# Hammerhead_-_MAX11300_Breakout_Connector.net
KiCad netlist of a schematic drawn in Altium Designer
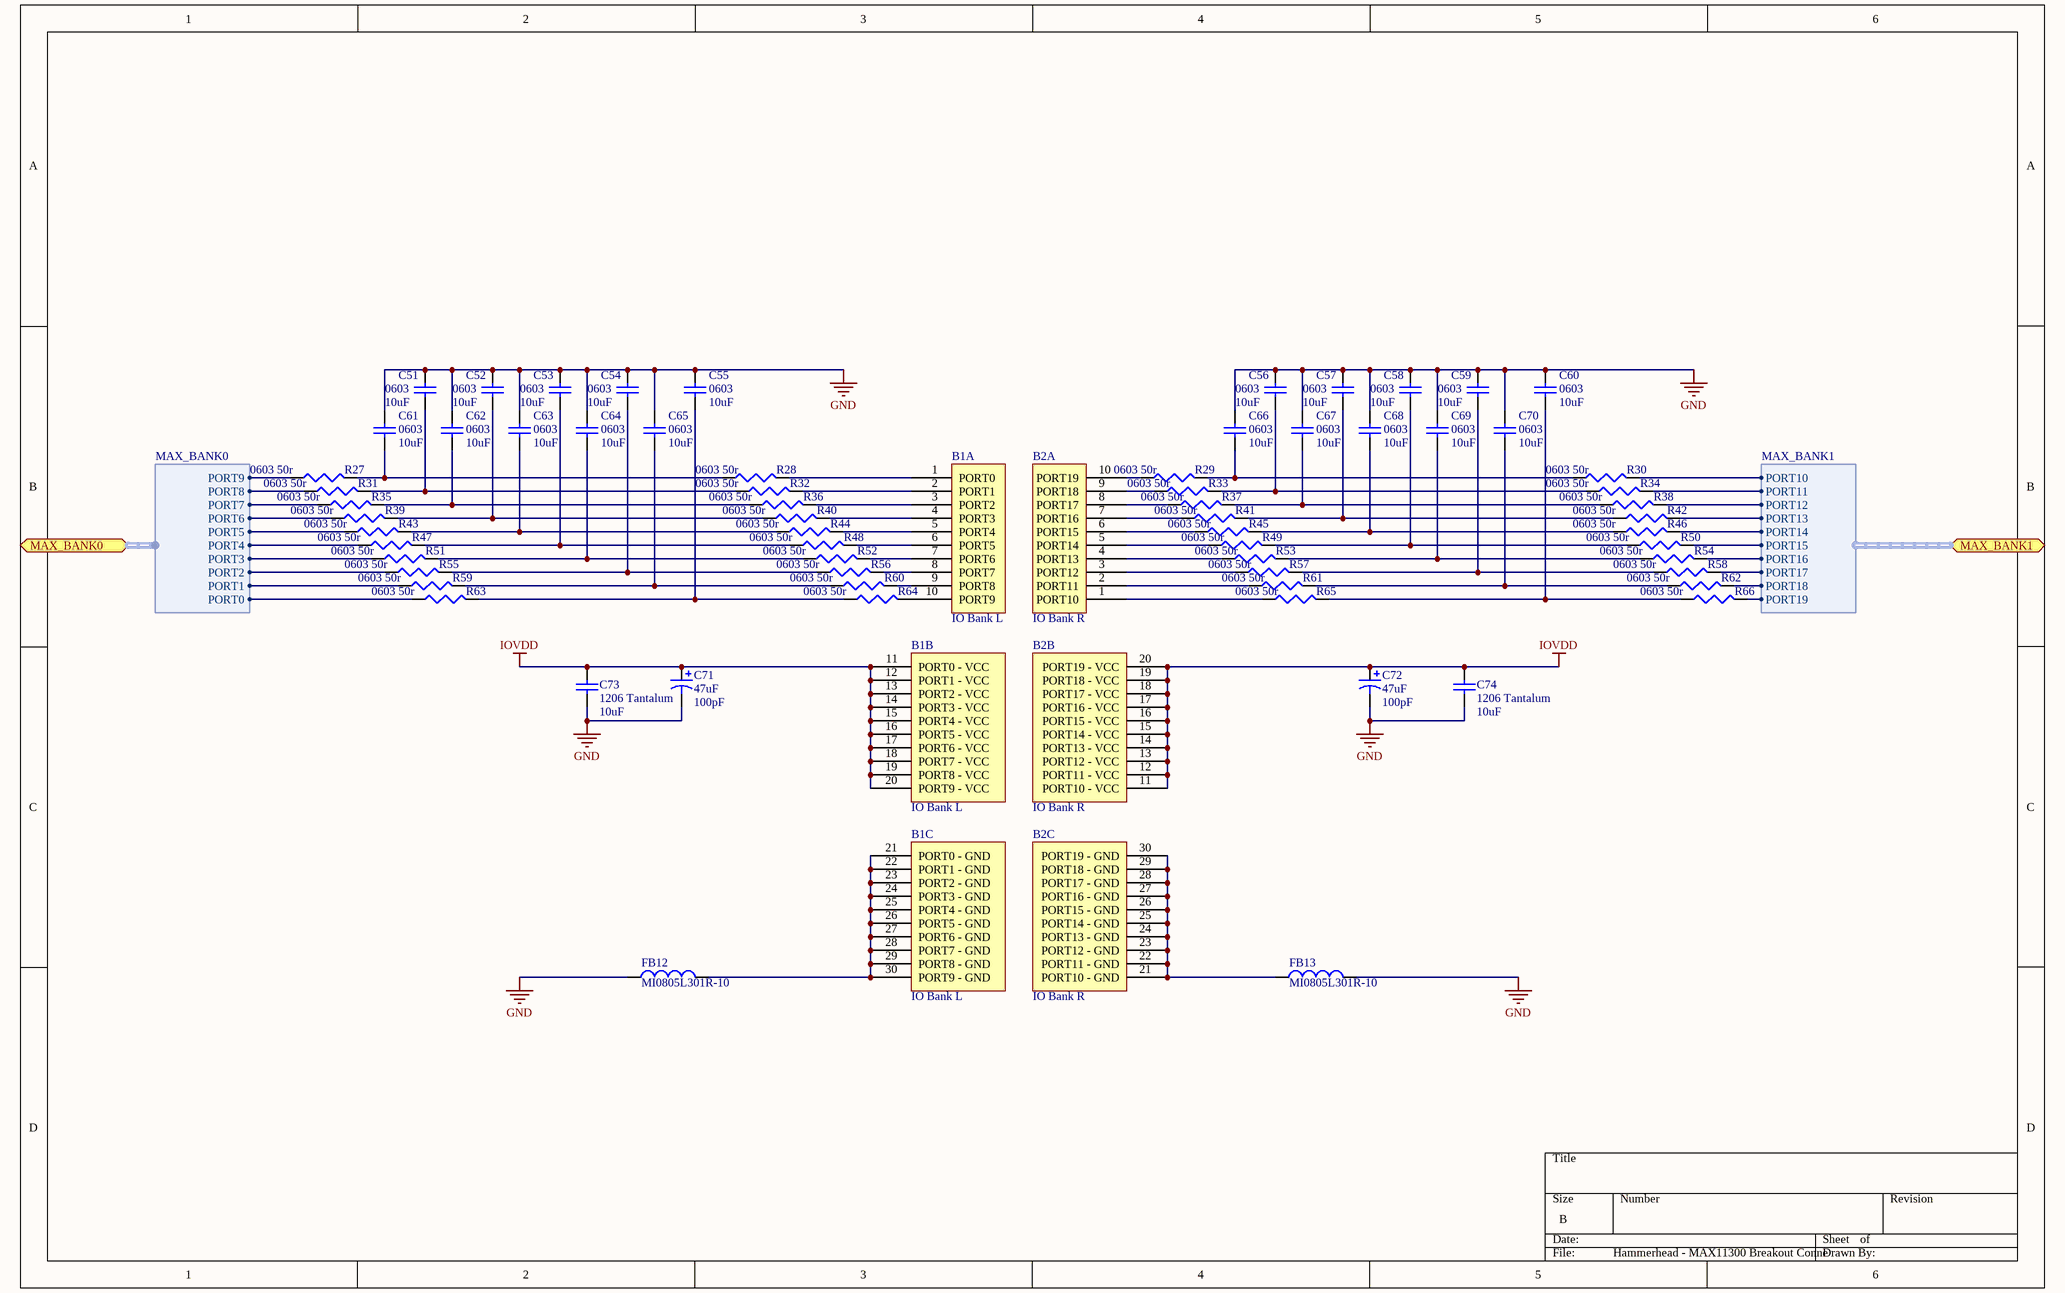
[diagram p0: Hammerhead - MAX11300 Breakout Connectors R1.1.SchDoc]

(export (version "E")
  (design (tool "Eeschema 10.0.6"))
  (components
    (comp (ref "B1")
      (value "IO Bank L")
      (footprint "2.54mm 10X3 Header")
      (libsource (lib "SunIO Schematic Symbol Lib") (part "IO Bank L"))
    )
    (comp (ref "B2")
      (value "IO Bank R")
      (footprint "2.54mm 10X3 Header")
      (libsource (lib "SunIO Schematic Symbol Lib") (part "IO Bank R"))
    )
    (comp (ref "C51")
      (value "0603")
      (footprint "1608[0603]")
      (description "Capacitor (Semiconductor SIM Model)")
      (fields (field (name "ALTIUM_VALUE") "10uF") (field (name "PUBLISHER") "Altium Limited"))
      (libsource (lib "Miscellaneous Devices") (part "Cap Semi"))
    )
    (comp (ref "C52")
      (value "0603")
      (footprint "1608[0603]")
      (description "Capacitor (Semiconductor SIM Model)")
      (fields (field (name "ALTIUM_VALUE") "10uF") (field (name "PUBLISHER") "Altium Limited"))
      (libsource (lib "Miscellaneous Devices") (part "Cap Semi"))
    )
    (comp (ref "C53")
      (value "0603")
      (footprint "1608[0603]")
      (description "Capacitor (Semiconductor SIM Model)")
      (fields (field (name "ALTIUM_VALUE") "10uF") (field (name "PUBLISHER") "Altium Limited"))
      (libsource (lib "Miscellaneous Devices") (part "Cap Semi"))
    )
    (comp (ref "C54")
      (value "0603")
      (footprint "1608[0603]")
      (description "Capacitor (Semiconductor SIM Model)")
      (fields (field (name "ALTIUM_VALUE") "10uF") (field (name "PUBLISHER") "Altium Limited"))
      (libsource (lib "Miscellaneous Devices") (part "Cap Semi"))
    )
    (comp (ref "C55")
      (value "0603")
      (footprint "1608[0603]")
      (description "Capacitor (Semiconductor SIM Model)")
      (fields (field (name "ALTIUM_VALUE") "10uF") (field (name "PUBLISHER") "Altium Limited"))
      (libsource (lib "Miscellaneous Devices") (part "Cap Semi"))
    )
    (comp (ref "C56")
      (value "0603")
      (footprint "1608[0603]")
      (description "Capacitor (Semiconductor SIM Model)")
      (fields (field (name "ALTIUM_VALUE") "10uF") (field (name "PUBLISHER") "Altium Limited"))
      (libsource (lib "Miscellaneous Devices") (part "Cap Semi"))
    )
    (comp (ref "C57")
      (value "0603")
      (footprint "1608[0603]")
      (description "Capacitor (Semiconductor SIM Model)")
      (fields (field (name "ALTIUM_VALUE") "10uF") (field (name "PUBLISHER") "Altium Limited"))
      (libsource (lib "Miscellaneous Devices") (part "Cap Semi"))
    )
    (comp (ref "C58")
      (value "0603")
      (footprint "1608[0603]")
      (description "Capacitor (Semiconductor SIM Model)")
      (fields (field (name "ALTIUM_VALUE") "10uF") (field (name "PUBLISHER") "Altium Limited"))
      (libsource (lib "Miscellaneous Devices") (part "Cap Semi"))
    )
    (comp (ref "C59")
      (value "0603")
      (footprint "1608[0603]")
      (description "Capacitor (Semiconductor SIM Model)")
      (fields (field (name "ALTIUM_VALUE") "10uF") (field (name "PUBLISHER") "Altium Limited"))
      (libsource (lib "Miscellaneous Devices") (part "Cap Semi"))
    )
    (comp (ref "C60")
      (value "0603")
      (footprint "1608[0603]")
      (description "Capacitor (Semiconductor SIM Model)")
      (fields (field (name "ALTIUM_VALUE") "10uF") (field (name "PUBLISHER") "Altium Limited"))
      (libsource (lib "Miscellaneous Devices") (part "Cap Semi"))
    )
    (comp (ref "C61")
      (value "0603")
      (footprint "1608[0603]")
      (description "Capacitor (Semiconductor SIM Model)")
      (fields (field (name "ALTIUM_VALUE") "10uF") (field (name "PUBLISHER") "Altium Limited"))
      (libsource (lib "Miscellaneous Devices") (part "Cap Semi"))
    )
    (comp (ref "C62")
      (value "0603")
      (footprint "1608[0603]")
      (description "Capacitor (Semiconductor SIM Model)")
      (fields (field (name "ALTIUM_VALUE") "10uF") (field (name "PUBLISHER") "Altium Limited"))
      (libsource (lib "Miscellaneous Devices") (part "Cap Semi"))
    )
    (comp (ref "C63")
      (value "0603")
      (footprint "1608[0603]")
      (description "Capacitor (Semiconductor SIM Model)")
      (fields (field (name "ALTIUM_VALUE") "10uF") (field (name "PUBLISHER") "Altium Limited"))
      (libsource (lib "Miscellaneous Devices") (part "Cap Semi"))
    )
    (comp (ref "C64")
      (value "0603")
      (footprint "1608[0603]")
      (description "Capacitor (Semiconductor SIM Model)")
      (fields (field (name "ALTIUM_VALUE") "10uF") (field (name "PUBLISHER") "Altium Limited"))
      (libsource (lib "Miscellaneous Devices") (part "Cap Semi"))
    )
    (comp (ref "C65")
      (value "0603")
      (footprint "1608[0603]")
      (description "Capacitor (Semiconductor SIM Model)")
      (fields (field (name "ALTIUM_VALUE") "10uF") (field (name "PUBLISHER") "Altium Limited"))
      (libsource (lib "Miscellaneous Devices") (part "Cap Semi"))
    )
    (comp (ref "C66")
      (value "0603")
      (footprint "1608[0603]")
      (description "Capacitor (Semiconductor SIM Model)")
      (fields (field (name "ALTIUM_VALUE") "10uF") (field (name "PUBLISHER") "Altium Limited"))
      (libsource (lib "Miscellaneous Devices") (part "Cap Semi"))
    )
    (comp (ref "C67")
      (value "0603")
      (footprint "1608[0603]")
      (description "Capacitor (Semiconductor SIM Model)")
      (fields (field (name "ALTIUM_VALUE") "10uF") (field (name "PUBLISHER") "Altium Limited"))
      (libsource (lib "Miscellaneous Devices") (part "Cap Semi"))
    )
    (comp (ref "C68")
      (value "0603")
      (footprint "1608[0603]")
      (description "Capacitor (Semiconductor SIM Model)")
      (fields (field (name "ALTIUM_VALUE") "10uF") (field (name "PUBLISHER") "Altium Limited"))
      (libsource (lib "Miscellaneous Devices") (part "Cap Semi"))
    )
    (comp (ref "C69")
      (value "0603")
      (footprint "1608[0603]")
      (description "Capacitor (Semiconductor SIM Model)")
      (fields (field (name "ALTIUM_VALUE") "10uF") (field (name "PUBLISHER") "Altium Limited"))
      (libsource (lib "Miscellaneous Devices") (part "Cap Semi"))
    )
    (comp (ref "C70")
      (value "0603")
      (footprint "1608[0603]")
      (description "Capacitor (Semiconductor SIM Model)")
      (fields (field (name "ALTIUM_VALUE") "10uF") (field (name "PUBLISHER") "Altium Limited"))
      (libsource (lib "Miscellaneous Devices") (part "Cap Semi"))
    )
    (comp (ref "C71")
      (value "47uF")
      (footprint "Panasonic VS C")
      (description "Polarized Capacitor (Radial)")
      (fields (field (name "ALTIUM_VALUE") "100pF") (field (name "PUBLISHER") "Altium Limited"))
      (libsource (lib "Miscellaneous Devices") (part "Cap Pol1"))
    )
    (comp (ref "C72")
      (value "47uF")
      (footprint "Panasonic VS C")
      (description "Polarized Capacitor (Radial)")
      (fields (field (name "ALTIUM_VALUE") "100pF") (field (name "PUBLISHER") "Altium Limited"))
      (libsource (lib "Miscellaneous Devices") (part "Cap Pol1"))
    )
    (comp (ref "C73")
      (value "1206 Tantalum")
      (footprint "C1206")
      (description "Capacitor (Semiconductor SIM Model)")
      (fields (field (name "ALTIUM_VALUE") "10uF") (field (name "PUBLISHER") "Altium Limited"))
      (libsource (lib "Miscellaneous Devices") (part "Cap Semi"))
    )
    (comp (ref "C74")
      (value "1206 Tantalum")
      (footprint "C1206")
      (description "Capacitor (Semiconductor SIM Model)")
      (fields (field (name "ALTIUM_VALUE") "10uF") (field (name "PUBLISHER") "Altium Limited"))
      (libsource (lib "Miscellaneous Devices") (part "Cap Semi"))
    )
    (comp (ref "FB12")
      (value "MI0805L301R-10")
      (footprint "SM 0805 - gap trimmed")
      (description "Inductor")
      (fields (field (name "PUBLISHER") "Altium Limited"))
      (libsource (lib "Miscellaneous Devices") (part "Inductor"))
    )
    (comp (ref "FB13")
      (value "MI0805L301R-10")
      (footprint "SM 0805 - gap trimmed")
      (description "Inductor")
      (fields (field (name "PUBLISHER") "Altium Limited"))
      (libsource (lib "Miscellaneous Devices") (part "Inductor"))
    )
    (comp (ref "R27")
      (value "0603")
      (footprint "J1-0603")
      (description "Resistor")
      (fields (field (name "ALTIUM_VALUE") "50r") (field (name "PUBLISHER") "Altium Limited"))
      (libsource (lib "Miscellaneous Devices") (part "Res3"))
    )
    (comp (ref "R28")
      (value "0603")
      (footprint "J1-0603")
      (description "Resistor")
      (fields (field (name "ALTIUM_VALUE") "50r") (field (name "PUBLISHER") "Altium Limited"))
      (libsource (lib "Miscellaneous Devices") (part "Res3"))
    )
    (comp (ref "R29")
      (value "0603")
      (footprint "J1-0603")
      (description "Resistor")
      (fields (field (name "ALTIUM_VALUE") "50r") (field (name "PUBLISHER") "Altium Limited"))
      (libsource (lib "Miscellaneous Devices") (part "Res3"))
    )
    (comp (ref "R30")
      (value "0603")
      (footprint "J1-0603")
      (description "Resistor")
      (fields (field (name "ALTIUM_VALUE") "50r") (field (name "PUBLISHER") "Altium Limited"))
      (libsource (lib "Miscellaneous Devices") (part "Res3"))
    )
    (comp (ref "R31")
      (value "0603")
      (footprint "J1-0603")
      (description "Resistor")
      (fields (field (name "ALTIUM_VALUE") "50r") (field (name "PUBLISHER") "Altium Limited"))
      (libsource (lib "Miscellaneous Devices") (part "Res3"))
    )
    (comp (ref "R32")
      (value "0603")
      (footprint "J1-0603")
      (description "Resistor")
      (fields (field (name "ALTIUM_VALUE") "50r") (field (name "PUBLISHER") "Altium Limited"))
      (libsource (lib "Miscellaneous Devices") (part "Res3"))
    )
    (comp (ref "R33")
      (value "0603")
      (footprint "J1-0603")
      (description "Resistor")
      (fields (field (name "ALTIUM_VALUE") "50r") (field (name "PUBLISHER") "Altium Limited"))
      (libsource (lib "Miscellaneous Devices") (part "Res3"))
    )
    (comp (ref "R34")
      (value "0603")
      (footprint "J1-0603")
      (description "Resistor")
      (fields (field (name "ALTIUM_VALUE") "50r") (field (name "PUBLISHER") "Altium Limited"))
      (libsource (lib "Miscellaneous Devices") (part "Res3"))
    )
    (comp (ref "R35")
      (value "0603")
      (footprint "J1-0603")
      (description "Resistor")
      (fields (field (name "ALTIUM_VALUE") "50r") (field (name "PUBLISHER") "Altium Limited"))
      (libsource (lib "Miscellaneous Devices") (part "Res3"))
    )
    (comp (ref "R36")
      (value "0603")
      (footprint "J1-0603")
      (description "Resistor")
      (fields (field (name "ALTIUM_VALUE") "50r") (field (name "PUBLISHER") "Altium Limited"))
      (libsource (lib "Miscellaneous Devices") (part "Res3"))
    )
    (comp (ref "R37")
      (value "0603")
      (footprint "J1-0603")
      (description "Resistor")
      (fields (field (name "ALTIUM_VALUE") "50r") (field (name "PUBLISHER") "Altium Limited"))
      (libsource (lib "Miscellaneous Devices") (part "Res3"))
    )
    (comp (ref "R38")
      (value "0603")
      (footprint "J1-0603")
      (description "Resistor")
      (fields (field (name "ALTIUM_VALUE") "50r") (field (name "PUBLISHER") "Altium Limited"))
      (libsource (lib "Miscellaneous Devices") (part "Res3"))
    )
    (comp (ref "R39")
      (value "0603")
      (footprint "J1-0603")
      (description "Resistor")
      (fields (field (name "ALTIUM_VALUE") "50r") (field (name "PUBLISHER") "Altium Limited"))
      (libsource (lib "Miscellaneous Devices") (part "Res3"))
    )
    (comp (ref "R40")
      (value "0603")
      (footprint "J1-0603")
      (description "Resistor")
      (fields (field (name "ALTIUM_VALUE") "50r") (field (name "PUBLISHER") "Altium Limited"))
      (libsource (lib "Miscellaneous Devices") (part "Res3"))
    )
    (comp (ref "R41")
      (value "0603")
      (footprint "J1-0603")
      (description "Resistor")
      (fields (field (name "ALTIUM_VALUE") "50r") (field (name "PUBLISHER") "Altium Limited"))
      (libsource (lib "Miscellaneous Devices") (part "Res3"))
    )
    (comp (ref "R42")
      (value "0603")
      (footprint "J1-0603")
      (description "Resistor")
      (fields (field (name "ALTIUM_VALUE") "50r") (field (name "PUBLISHER") "Altium Limited"))
      (libsource (lib "Miscellaneous Devices") (part "Res3"))
    )
    (comp (ref "R43")
      (value "0603")
      (footprint "J1-0603")
      (description "Resistor")
      (fields (field (name "ALTIUM_VALUE") "50r") (field (name "PUBLISHER") "Altium Limited"))
      (libsource (lib "Miscellaneous Devices") (part "Res3"))
    )
    (comp (ref "R44")
      (value "0603")
      (footprint "J1-0603")
      (description "Resistor")
      (fields (field (name "ALTIUM_VALUE") "50r") (field (name "PUBLISHER") "Altium Limited"))
      (libsource (lib "Miscellaneous Devices") (part "Res3"))
    )
    (comp (ref "R45")
      (value "0603")
      (footprint "J1-0603")
      (description "Resistor")
      (fields (field (name "ALTIUM_VALUE") "50r") (field (name "PUBLISHER") "Altium Limited"))
      (libsource (lib "Miscellaneous Devices") (part "Res3"))
    )
    (comp (ref "R46")
      (value "0603")
      (footprint "J1-0603")
      (description "Resistor")
      (fields (field (name "ALTIUM_VALUE") "50r") (field (name "PUBLISHER") "Altium Limited"))
      (libsource (lib "Miscellaneous Devices") (part "Res3"))
    )
    (comp (ref "R47")
      (value "0603")
      (footprint "J1-0603")
      (description "Resistor")
      (fields (field (name "ALTIUM_VALUE") "50r") (field (name "PUBLISHER") "Altium Limited"))
      (libsource (lib "Miscellaneous Devices") (part "Res3"))
    )
    (comp (ref "R48")
      (value "0603")
      (footprint "J1-0603")
      (description "Resistor")
      (fields (field (name "ALTIUM_VALUE") "50r") (field (name "PUBLISHER") "Altium Limited"))
      (libsource (lib "Miscellaneous Devices") (part "Res3"))
    )
    (comp (ref "R49")
      (value "0603")
      (footprint "J1-0603")
      (description "Resistor")
      (fields (field (name "ALTIUM_VALUE") "50r") (field (name "PUBLISHER") "Altium Limited"))
      (libsource (lib "Miscellaneous Devices") (part "Res3"))
    )
    (comp (ref "R50")
      (value "0603")
      (footprint "J1-0603")
      (description "Resistor")
      (fields (field (name "ALTIUM_VALUE") "50r") (field (name "PUBLISHER") "Altium Limited"))
      (libsource (lib "Miscellaneous Devices") (part "Res3"))
    )
    (comp (ref "R51")
      (value "0603")
      (footprint "J1-0603")
      (description "Resistor")
      (fields (field (name "ALTIUM_VALUE") "50r") (field (name "PUBLISHER") "Altium Limited"))
      (libsource (lib "Miscellaneous Devices") (part "Res3"))
    )
    (comp (ref "R52")
      (value "0603")
      (footprint "J1-0603")
      (description "Resistor")
      (fields (field (name "ALTIUM_VALUE") "50r") (field (name "PUBLISHER") "Altium Limited"))
      (libsource (lib "Miscellaneous Devices") (part "Res3"))
    )
    (comp (ref "R53")
      (value "0603")
      (footprint "J1-0603")
      (description "Resistor")
      (fields (field (name "ALTIUM_VALUE") "50r") (field (name "PUBLISHER") "Altium Limited"))
      (libsource (lib "Miscellaneous Devices") (part "Res3"))
    )
    (comp (ref "R54")
      (value "0603")
      (footprint "J1-0603")
      (description "Resistor")
      (fields (field (name "ALTIUM_VALUE") "50r") (field (name "PUBLISHER") "Altium Limited"))
      (libsource (lib "Miscellaneous Devices") (part "Res3"))
    )
    (comp (ref "R55")
      (value "0603")
      (footprint "J1-0603")
      (description "Resistor")
      (fields (field (name "ALTIUM_VALUE") "50r") (field (name "PUBLISHER") "Altium Limited"))
      (libsource (lib "Miscellaneous Devices") (part "Res3"))
    )
    (comp (ref "R56")
      (value "0603")
      (footprint "J1-0603")
      (description "Resistor")
      (fields (field (name "ALTIUM_VALUE") "50r") (field (name "PUBLISHER") "Altium Limited"))
      (libsource (lib "Miscellaneous Devices") (part "Res3"))
    )
    (comp (ref "R57")
      (value "0603")
      (footprint "J1-0603")
      (description "Resistor")
      (fields (field (name "ALTIUM_VALUE") "50r") (field (name "PUBLISHER") "Altium Limited"))
      (libsource (lib "Miscellaneous Devices") (part "Res3"))
    )
    (comp (ref "R58")
      (value "0603")
      (footprint "J1-0603")
      (description "Resistor")
      (fields (field (name "ALTIUM_VALUE") "50r") (field (name "PUBLISHER") "Altium Limited"))
      (libsource (lib "Miscellaneous Devices") (part "Res3"))
    )
    (comp (ref "R59")
      (value "0603")
      (footprint "J1-0603")
      (description "Resistor")
      (fields (field (name "ALTIUM_VALUE") "50r") (field (name "PUBLISHER") "Altium Limited"))
      (libsource (lib "Miscellaneous Devices") (part "Res3"))
    )
    (comp (ref "R60")
      (value "0603")
      (footprint "J1-0603")
      (description "Resistor")
      (fields (field (name "ALTIUM_VALUE") "50r") (field (name "PUBLISHER") "Altium Limited"))
      (libsource (lib "Miscellaneous Devices") (part "Res3"))
    )
    (comp (ref "R61")
      (value "0603")
      (footprint "J1-0603")
      (description "Resistor")
      (fields (field (name "ALTIUM_VALUE") "50r") (field (name "PUBLISHER") "Altium Limited"))
      (libsource (lib "Miscellaneous Devices") (part "Res3"))
    )
    (comp (ref "R62")
      (value "0603")
      (footprint "J1-0603")
      (description "Resistor")
      (fields (field (name "ALTIUM_VALUE") "50r") (field (name "PUBLISHER") "Altium Limited"))
      (libsource (lib "Miscellaneous Devices") (part "Res3"))
    )
    (comp (ref "R63")
      (value "0603")
      (footprint "J1-0603")
      (description "Resistor")
      (fields (field (name "ALTIUM_VALUE") "50r") (field (name "PUBLISHER") "Altium Limited"))
      (libsource (lib "Miscellaneous Devices") (part "Res3"))
    )
    (comp (ref "R64")
      (value "0603")
      (footprint "J1-0603")
      (description "Resistor")
      (fields (field (name "ALTIUM_VALUE") "50r") (field (name "PUBLISHER") "Altium Limited"))
      (libsource (lib "Miscellaneous Devices") (part "Res3"))
    )
    (comp (ref "R65")
      (value "0603")
      (footprint "J1-0603")
      (description "Resistor")
      (fields (field (name "ALTIUM_VALUE") "50r") (field (name "PUBLISHER") "Altium Limited"))
      (libsource (lib "Miscellaneous Devices") (part "Res3"))
    )
    (comp (ref "R66")
      (value "0603")
      (footprint "J1-0603")
      (description "Resistor")
      (fields (field (name "ALTIUM_VALUE") "50r") (field (name "PUBLISHER") "Altium Limited"))
      (libsource (lib "Miscellaneous Devices") (part "Res3"))
    )
  )
  (nets
    (net (code "3") (name "/PORT0") (class "Default")
      (node (ref "R63") (pin "1") (pinfunction "1_1") (pintype "passive"))
    )
    (net (code "4") (name "/PORT1") (class "Default")
      (node (ref "R59") (pin "1") (pinfunction "1_1") (pintype "passive"))
    )
    (net (code "5") (name "/PORT2") (class "Default")
      (node (ref "R55") (pin "1") (pinfunction "1_1") (pintype "passive"))
    )
    (net (code "6") (name "/PORT3") (class "Default")
      (node (ref "R51") (pin "1") (pinfunction "1_1") (pintype "passive"))
    )
    (net (code "7") (name "/PORT4") (class "Default")
      (node (ref "R47") (pin "1") (pinfunction "1_1") (pintype "passive"))
    )
    (net (code "8") (name "/PORT5") (class "Default")
      (node (ref "R43") (pin "1") (pinfunction "1_1") (pintype "passive"))
    )
    (net (code "9") (name "/PORT6") (class "Default")
      (node (ref "R39") (pin "1") (pinfunction "1_1") (pintype "passive"))
    )
    (net (code "10") (name "/PORT7") (class "Default")
      (node (ref "R35") (pin "1") (pinfunction "1_1") (pintype "passive"))
    )
    (net (code "11") (name "/PORT8") (class "Default")
      (node (ref "R31") (pin "1") (pinfunction "1_1") (pintype "passive"))
    )
    (net (code "12") (name "/PORT9") (class "Default")
      (node (ref "R27") (pin "1") (pinfunction "1_1") (pintype "passive"))
    )
    (net (code "13") (name "/PORT10") (class "Default")
      (node (ref "R30") (pin "2") (pinfunction "2_2") (pintype "passive"))
    )
    (net (code "14") (name "/PORT11") (class "Default")
      (node (ref "R34") (pin "2") (pinfunction "2_2") (pintype "passive"))
    )
    (net (code "15") (name "/PORT12") (class "Default")
      (node (ref "R38") (pin "2") (pinfunction "2_2") (pintype "passive"))
    )
    (net (code "16") (name "/PORT13") (class "Default")
      (node (ref "R42") (pin "2") (pinfunction "2_2") (pintype "passive"))
    )
    (net (code "17") (name "/PORT14") (class "Default")
      (node (ref "R46") (pin "2") (pinfunction "2_2") (pintype "passive"))
    )
    (net (code "18") (name "/PORT15") (class "Default")
      (node (ref "R50") (pin "2") (pinfunction "2_2") (pintype "passive"))
    )
    (net (code "19") (name "/PORT16") (class "Default")
      (node (ref "R54") (pin "2") (pinfunction "2_2") (pintype "passive"))
    )
    (net (code "20") (name "/PORT17") (class "Default")
      (node (ref "R58") (pin "2") (pinfunction "2_2") (pintype "passive"))
    )
    (net (code "21") (name "/PORT18") (class "Default")
      (node (ref "R62") (pin "2") (pinfunction "2_2") (pintype "passive"))
    )
    (net (code "22") (name "/PORT19") (class "Default")
      (node (ref "R66") (pin "2") (pinfunction "2_2") (pintype "passive"))
    )
    (net (code "25") (name "GND") (class "Default")
      (node (ref "C51") (pin "2") (pinfunction "2_2") (pintype "passive"))
      (node (ref "C52") (pin "2") (pinfunction "2_2") (pintype "passive"))
      (node (ref "C53") (pin "2") (pinfunction "2_2") (pintype "passive"))
      (node (ref "C54") (pin "2") (pinfunction "2_2") (pintype "passive"))
      (node (ref "C55") (pin "2") (pinfunction "2_2") (pintype "passive"))
      (node (ref "C56") (pin "2") (pinfunction "2_2") (pintype "passive"))
      (node (ref "C57") (pin "2") (pinfunction "2_2") (pintype "passive"))
      (node (ref "C58") (pin "2") (pinfunction "2_2") (pintype "passive"))
      (node (ref "C59") (pin "2") (pinfunction "2_2") (pintype "passive"))
      (node (ref "C60") (pin "2") (pinfunction "2_2") (pintype "passive"))
      (node (ref "C61") (pin "2") (pinfunction "2_2") (pintype "passive"))
      (node (ref "C62") (pin "2") (pinfunction "2_2") (pintype "passive"))
      (node (ref "C63") (pin "2") (pinfunction "2_2") (pintype "passive"))
      (node (ref "C64") (pin "2") (pinfunction "2_2") (pintype "passive"))
      (node (ref "C65") (pin "2") (pinfunction "2_2") (pintype "passive"))
      (node (ref "C66") (pin "2") (pinfunction "2_2") (pintype "passive"))
      (node (ref "C67") (pin "2") (pinfunction "2_2") (pintype "passive"))
      (node (ref "C68") (pin "2") (pinfunction "2_2") (pintype "passive"))
      (node (ref "C69") (pin "2") (pinfunction "2_2") (pintype "passive"))
      (node (ref "C70") (pin "2") (pinfunction "2_2") (pintype "passive"))
      (node (ref "C71") (pin "2") (pinfunction "2_2") (pintype "passive"))
      (node (ref "C72") (pin "2") (pinfunction "2_2") (pintype "passive"))
      (node (ref "C73") (pin "1") (pinfunction "1_1") (pintype "passive"))
      (node (ref "C74") (pin "1") (pinfunction "1_1") (pintype "passive"))
      (node (ref "FB12") (pin "1") (pinfunction "1_1") (pintype "passive"))
      (node (ref "FB13") (pin "2") (pinfunction "2_2") (pintype "passive"))
    )
    (net (code "26") (name "IOVDD") (class "Default")
      (node (ref "B1") (pin "11") (pinfunction "PORT0_-_VCC_11") (pintype "passive"))
      (node (ref "B1") (pin "12") (pinfunction "PORT1_-_VCC_12") (pintype "passive"))
      (node (ref "B1") (pin "13") (pinfunction "PORT2_-_VCC_13") (pintype "passive"))
      (node (ref "B1") (pin "14") (pinfunction "PORT3_-_VCC_14") (pintype "passive"))
      (node (ref "B1") (pin "15") (pinfunction "PORT4_-_VCC_15") (pintype "passive"))
      (node (ref "B1") (pin "16") (pinfunction "PORT5_-_VCC_16") (pintype "passive"))
      (node (ref "B1") (pin "17") (pinfunction "PORT6_-_VCC_17") (pintype "passive"))
      (node (ref "B1") (pin "18") (pinfunction "PORT7_-_VCC_18") (pintype "passive"))
      (node (ref "B1") (pin "19") (pinfunction "PORT8_-_VCC_19") (pintype "passive"))
      (node (ref "B1") (pin "20") (pinfunction "PORT9_-_VCC_20") (pintype "passive"))
      (node (ref "B2") (pin "11") (pinfunction "PORT10_-_VCC_11") (pintype "passive"))
      (node (ref "B2") (pin "12") (pinfunction "PORT11_-_VCC_12") (pintype "passive"))
      (node (ref "B2") (pin "13") (pinfunction "PORT12_-_VCC_13") (pintype "passive"))
      (node (ref "B2") (pin "14") (pinfunction "PORT13_-_VCC_14") (pintype "passive"))
      (node (ref "B2") (pin "15") (pinfunction "PORT14_-_VCC_15") (pintype "passive"))
      (node (ref "B2") (pin "16") (pinfunction "PORT15_-_VCC_16") (pintype "passive"))
      (node (ref "B2") (pin "17") (pinfunction "PORT16_-_VCC_17") (pintype "passive"))
      (node (ref "B2") (pin "18") (pinfunction "PORT17_-_VCC_18") (pintype "passive"))
      (node (ref "B2") (pin "19") (pinfunction "PORT18_-_VCC_19") (pintype "passive"))
      (node (ref "B2") (pin "20") (pinfunction "PORT19_-_VCC_20") (pintype "passive"))
      (node (ref "C71") (pin "1") (pinfunction "1_1") (pintype "passive"))
      (node (ref "C72") (pin "1") (pinfunction "1_1") (pintype "passive"))
      (node (ref "C73") (pin "2") (pinfunction "2_2") (pintype "passive"))
      (node (ref "C74") (pin "2") (pinfunction "2_2") (pintype "passive"))
    )
    (net (code "27") (name "Net-(B1A-PORT0)") (class "Default")
      (node (ref "B1") (pin "1") (pinfunction "PORT0_1") (pintype "passive"))
      (node (ref "R28") (pin "2") (pinfunction "2_2") (pintype "passive"))
    )
    (net (code "28") (name "Net-(B1A-PORT1)") (class "Default")
      (node (ref "B1") (pin "2") (pinfunction "PORT1_2") (pintype "passive"))
      (node (ref "R32") (pin "2") (pinfunction "2_2") (pintype "passive"))
    )
    (net (code "29") (name "Net-(B1A-PORT2)") (class "Default")
      (node (ref "B1") (pin "3") (pinfunction "PORT2_3") (pintype "passive"))
      (node (ref "R36") (pin "2") (pinfunction "2_2") (pintype "passive"))
    )
    (net (code "30") (name "Net-(B1A-PORT3)") (class "Default")
      (node (ref "B1") (pin "4") (pinfunction "PORT3_4") (pintype "passive"))
      (node (ref "R40") (pin "2") (pinfunction "2_2") (pintype "passive"))
    )
    (net (code "31") (name "Net-(B1A-PORT4)") (class "Default")
      (node (ref "B1") (pin "5") (pinfunction "PORT4_5") (pintype "passive"))
      (node (ref "R44") (pin "2") (pinfunction "2_2") (pintype "passive"))
    )
    (net (code "32") (name "Net-(B1A-PORT5)") (class "Default")
      (node (ref "B1") (pin "6") (pinfunction "PORT5_6") (pintype "passive"))
      (node (ref "R48") (pin "2") (pinfunction "2_2") (pintype "passive"))
    )
    (net (code "33") (name "Net-(B1A-PORT6)") (class "Default")
      (node (ref "B1") (pin "7") (pinfunction "PORT6_7") (pintype "passive"))
      (node (ref "R52") (pin "2") (pinfunction "2_2") (pintype "passive"))
    )
    (net (code "34") (name "Net-(B1A-PORT7)") (class "Default")
      (node (ref "B1") (pin "8") (pinfunction "PORT7_8") (pintype "passive"))
      (node (ref "R56") (pin "2") (pinfunction "2_2") (pintype "passive"))
    )
    (net (code "35") (name "Net-(B1A-PORT8)") (class "Default")
      (node (ref "B1") (pin "9") (pinfunction "PORT8_9") (pintype "passive"))
      (node (ref "R60") (pin "2") (pinfunction "2_2") (pintype "passive"))
    )
    (net (code "36") (name "Net-(B1A-PORT9)") (class "Default")
      (node (ref "B1") (pin "10") (pinfunction "PORT9_10") (pintype "passive"))
      (node (ref "R64") (pin "2") (pinfunction "2_2") (pintype "passive"))
    )
    (net (code "37") (name "Net-(B1C-PORT0_-_GND)") (class "Default")
      (node (ref "B1") (pin "21") (pinfunction "PORT0_-_GND_21") (pintype "passive"))
      (node (ref "B1") (pin "22") (pinfunction "PORT1_-_GND_22") (pintype "passive"))
      (node (ref "B1") (pin "23") (pinfunction "PORT2_-_GND_23") (pintype "passive"))
      (node (ref "B1") (pin "24") (pinfunction "PORT3_-_GND_24") (pintype "passive"))
      (node (ref "B1") (pin "25") (pinfunction "PORT4_-_GND_25") (pintype "passive"))
      (node (ref "B1") (pin "26") (pinfunction "PORT5_-_GND_26") (pintype "passive"))
      (node (ref "B1") (pin "27") (pinfunction "PORT6_-_GND_27") (pintype "passive"))
      (node (ref "B1") (pin "28") (pinfunction "PORT7_-_GND_28") (pintype "passive"))
      (node (ref "B1") (pin "29") (pinfunction "PORT8_-_GND_29") (pintype "passive"))
      (node (ref "B1") (pin "30") (pinfunction "PORT9_-_GND_30") (pintype "passive"))
      (node (ref "FB12") (pin "2") (pinfunction "2_2") (pintype "passive"))
    )
    (net (code "38") (name "Net-(B2A-PORT10)") (class "Default")
      (node (ref "B2") (pin "1") (pinfunction "PORT10_1") (pintype "passive"))
      (node (ref "R65") (pin "1") (pinfunction "1_1") (pintype "passive"))
    )
    (net (code "39") (name "Net-(B2A-PORT11)") (class "Default")
      (node (ref "B2") (pin "2") (pinfunction "PORT11_2") (pintype "passive"))
      (node (ref "R61") (pin "1") (pinfunction "1_1") (pintype "passive"))
    )
    (net (code "40") (name "Net-(B2A-PORT12)") (class "Default")
      (node (ref "B2") (pin "3") (pinfunction "PORT12_3") (pintype "passive"))
      (node (ref "R57") (pin "1") (pinfunction "1_1") (pintype "passive"))
    )
    (net (code "41") (name "Net-(B2A-PORT13)") (class "Default")
      (node (ref "B2") (pin "4") (pinfunction "PORT13_4") (pintype "passive"))
      (node (ref "R53") (pin "1") (pinfunction "1_1") (pintype "passive"))
    )
    (net (code "42") (name "Net-(B2A-PORT14)") (class "Default")
      (node (ref "B2") (pin "5") (pinfunction "PORT14_5") (pintype "passive"))
      (node (ref "R49") (pin "1") (pinfunction "1_1") (pintype "passive"))
    )
    (net (code "43") (name "Net-(B2A-PORT15)") (class "Default")
      (node (ref "B2") (pin "6") (pinfunction "PORT15_6") (pintype "passive"))
      (node (ref "R45") (pin "1") (pinfunction "1_1") (pintype "passive"))
    )
    (net (code "44") (name "Net-(B2A-PORT16)") (class "Default")
      (node (ref "B2") (pin "7") (pinfunction "PORT16_7") (pintype "passive"))
      (node (ref "R41") (pin "1") (pinfunction "1_1") (pintype "passive"))
    )
    (net (code "45") (name "Net-(B2A-PORT17)") (class "Default")
      (node (ref "B2") (pin "8") (pinfunction "PORT17_8") (pintype "passive"))
      (node (ref "R37") (pin "1") (pinfunction "1_1") (pintype "passive"))
    )
    (net (code "46") (name "Net-(B2A-PORT18)") (class "Default")
      (node (ref "B2") (pin "9") (pinfunction "PORT18_9") (pintype "passive"))
      (node (ref "R33") (pin "1") (pinfunction "1_1") (pintype "passive"))
    )
    (net (code "47") (name "Net-(B2A-PORT19)") (class "Default")
      (node (ref "B2") (pin "10") (pinfunction "PORT19_10") (pintype "passive"))
      (node (ref "R29") (pin "1") (pinfunction "1_1") (pintype "passive"))
    )
    (net (code "48") (name "Net-(B2C-PORT10_-_GND)") (class "Default")
      (node (ref "B2") (pin "21") (pinfunction "PORT10_-_GND_21") (pintype "passive"))
      (node (ref "B2") (pin "22") (pinfunction "PORT11_-_GND_22") (pintype "passive"))
      (node (ref "B2") (pin "23") (pinfunction "PORT12_-_GND_23") (pintype "passive"))
      (node (ref "B2") (pin "24") (pinfunction "PORT13_-_GND_24") (pintype "passive"))
      (node (ref "B2") (pin "25") (pinfunction "PORT14_-_GND_25") (pintype "passive"))
      (node (ref "B2") (pin "26") (pinfunction "PORT15_-_GND_26") (pintype "passive"))
      (node (ref "B2") (pin "27") (pinfunction "PORT16_-_GND_27") (pintype "passive"))
      (node (ref "B2") (pin "28") (pinfunction "PORT17_-_GND_28") (pintype "passive"))
      (node (ref "B2") (pin "29") (pinfunction "PORT18_-_GND_29") (pintype "passive"))
      (node (ref "B2") (pin "30") (pinfunction "PORT19_-_GND_30") (pintype "passive"))
      (node (ref "FB13") (pin "1") (pinfunction "1_1") (pintype "passive"))
    )
    (net (code "49") (name "Net-(C51-Pad1)") (class "Default")
      (node (ref "C51") (pin "1") (pinfunction "1_1") (pintype "passive"))
      (node (ref "R31") (pin "2") (pinfunction "2_2") (pintype "passive"))
      (node (ref "R32") (pin "1") (pinfunction "1_1") (pintype "passive"))
    )
    (net (code "50") (name "Net-(C52-Pad1)") (class "Default")
      (node (ref "C52") (pin "1") (pinfunction "1_1") (pintype "passive"))
      (node (ref "R39") (pin "2") (pinfunction "2_2") (pintype "passive"))
      (node (ref "R40") (pin "1") (pinfunction "1_1") (pintype "passive"))
    )
    (net (code "51") (name "Net-(C53-Pad1)") (class "Default")
      (node (ref "C53") (pin "1") (pinfunction "1_1") (pintype "passive"))
      (node (ref "R47") (pin "2") (pinfunction "2_2") (pintype "passive"))
      (node (ref "R48") (pin "1") (pinfunction "1_1") (pintype "passive"))
    )
    (net (code "52") (name "Net-(C54-Pad1)") (class "Default")
      (node (ref "C54") (pin "1") (pinfunction "1_1") (pintype "passive"))
      (node (ref "R55") (pin "2") (pinfunction "2_2") (pintype "passive"))
      (node (ref "R56") (pin "1") (pinfunction "1_1") (pintype "passive"))
    )
    (net (code "53") (name "Net-(C55-Pad1)") (class "Default")
      (node (ref "C55") (pin "1") (pinfunction "1_1") (pintype "passive"))
      (node (ref "R63") (pin "2") (pinfunction "2_2") (pintype "passive"))
      (node (ref "R64") (pin "1") (pinfunction "1_1") (pintype "passive"))
    )
    (net (code "54") (name "Net-(C56-Pad1)") (class "Default")
      (node (ref "C56") (pin "1") (pinfunction "1_1") (pintype "passive"))
      (node (ref "R33") (pin "2") (pinfunction "2_2") (pintype "passive"))
      (node (ref "R34") (pin "1") (pinfunction "1_1") (pintype "passive"))
    )
    (net (code "55") (name "Net-(C57-Pad1)") (class "Default")
      (node (ref "C57") (pin "1") (pinfunction "1_1") (pintype "passive"))
      (node (ref "R41") (pin "2") (pinfunction "2_2") (pintype "passive"))
      (node (ref "R42") (pin "1") (pinfunction "1_1") (pintype "passive"))
    )
    (net (code "56") (name "Net-(C58-Pad1)") (class "Default")
      (node (ref "C58") (pin "1") (pinfunction "1_1") (pintype "passive"))
      (node (ref "R49") (pin "2") (pinfunction "2_2") (pintype "passive"))
      (node (ref "R50") (pin "1") (pinfunction "1_1") (pintype "passive"))
    )
    (net (code "57") (name "Net-(C59-Pad1)") (class "Default")
      (node (ref "C59") (pin "1") (pinfunction "1_1") (pintype "passive"))
      (node (ref "R57") (pin "2") (pinfunction "2_2") (pintype "passive"))
      (node (ref "R58") (pin "1") (pinfunction "1_1") (pintype "passive"))
    )
    (net (code "58") (name "Net-(C60-Pad1)") (class "Default")
      (node (ref "C60") (pin "1") (pinfunction "1_1") (pintype "passive"))
      (node (ref "R65") (pin "2") (pinfunction "2_2") (pintype "passive"))
      (node (ref "R66") (pin "1") (pinfunction "1_1") (pintype "passive"))
    )
    (net (code "59") (name "Net-(C61-Pad1)") (class "Default")
      (node (ref "C61") (pin "1") (pinfunction "1_1") (pintype "passive"))
      (node (ref "R27") (pin "2") (pinfunction "2_2") (pintype "passive"))
      (node (ref "R28") (pin "1") (pinfunction "1_1") (pintype "passive"))
    )
    (net (code "60") (name "Net-(C62-Pad1)") (class "Default")
      (node (ref "C62") (pin "1") (pinfunction "1_1") (pintype "passive"))
      (node (ref "R35") (pin "2") (pinfunction "2_2") (pintype "passive"))
      (node (ref "R36") (pin "1") (pinfunction "1_1") (pintype "passive"))
    )
    (net (code "61") (name "Net-(C63-Pad1)") (class "Default")
      (node (ref "C63") (pin "1") (pinfunction "1_1") (pintype "passive"))
      (node (ref "R43") (pin "2") (pinfunction "2_2") (pintype "passive"))
      (node (ref "R44") (pin "1") (pinfunction "1_1") (pintype "passive"))
    )
    (net (code "62") (name "Net-(C64-Pad1)") (class "Default")
      (node (ref "C64") (pin "1") (pinfunction "1_1") (pintype "passive"))
      (node (ref "R51") (pin "2") (pinfunction "2_2") (pintype "passive"))
      (node (ref "R52") (pin "1") (pinfunction "1_1") (pintype "passive"))
    )
    (net (code "63") (name "Net-(C65-Pad1)") (class "Default")
      (node (ref "C65") (pin "1") (pinfunction "1_1") (pintype "passive"))
      (node (ref "R59") (pin "2") (pinfunction "2_2") (pintype "passive"))
      (node (ref "R60") (pin "1") (pinfunction "1_1") (pintype "passive"))
    )
    (net (code "64") (name "Net-(C66-Pad1)") (class "Default")
      (node (ref "C66") (pin "1") (pinfunction "1_1") (pintype "passive"))
      (node (ref "R29") (pin "2") (pinfunction "2_2") (pintype "passive"))
      (node (ref "R30") (pin "1") (pinfunction "1_1") (pintype "passive"))
    )
    (net (code "65") (name "Net-(C67-Pad1)") (class "Default")
      (node (ref "C67") (pin "1") (pinfunction "1_1") (pintype "passive"))
      (node (ref "R37") (pin "2") (pinfunction "2_2") (pintype "passive"))
      (node (ref "R38") (pin "1") (pinfunction "1_1") (pintype "passive"))
    )
    (net (code "66") (name "Net-(C68-Pad1)") (class "Default")
      (node (ref "C68") (pin "1") (pinfunction "1_1") (pintype "passive"))
      (node (ref "R45") (pin "2") (pinfunction "2_2") (pintype "passive"))
      (node (ref "R46") (pin "1") (pinfunction "1_1") (pintype "passive"))
    )
    (net (code "67") (name "Net-(C69-Pad1)") (class "Default")
      (node (ref "C69") (pin "1") (pinfunction "1_1") (pintype "passive"))
      (node (ref "R53") (pin "2") (pinfunction "2_2") (pintype "passive"))
      (node (ref "R54") (pin "1") (pinfunction "1_1") (pintype "passive"))
    )
    (net (code "68") (name "Net-(C70-Pad1)") (class "Default")
      (node (ref "C70") (pin "1") (pinfunction "1_1") (pintype "passive"))
      (node (ref "R61") (pin "2") (pinfunction "2_2") (pintype "passive"))
      (node (ref "R62") (pin "1") (pinfunction "1_1") (pintype "passive"))
    )
  )
)
